# RCMX_Rev_00_BPS.net
KiCad netlist of a schematic drawn in EAGLE
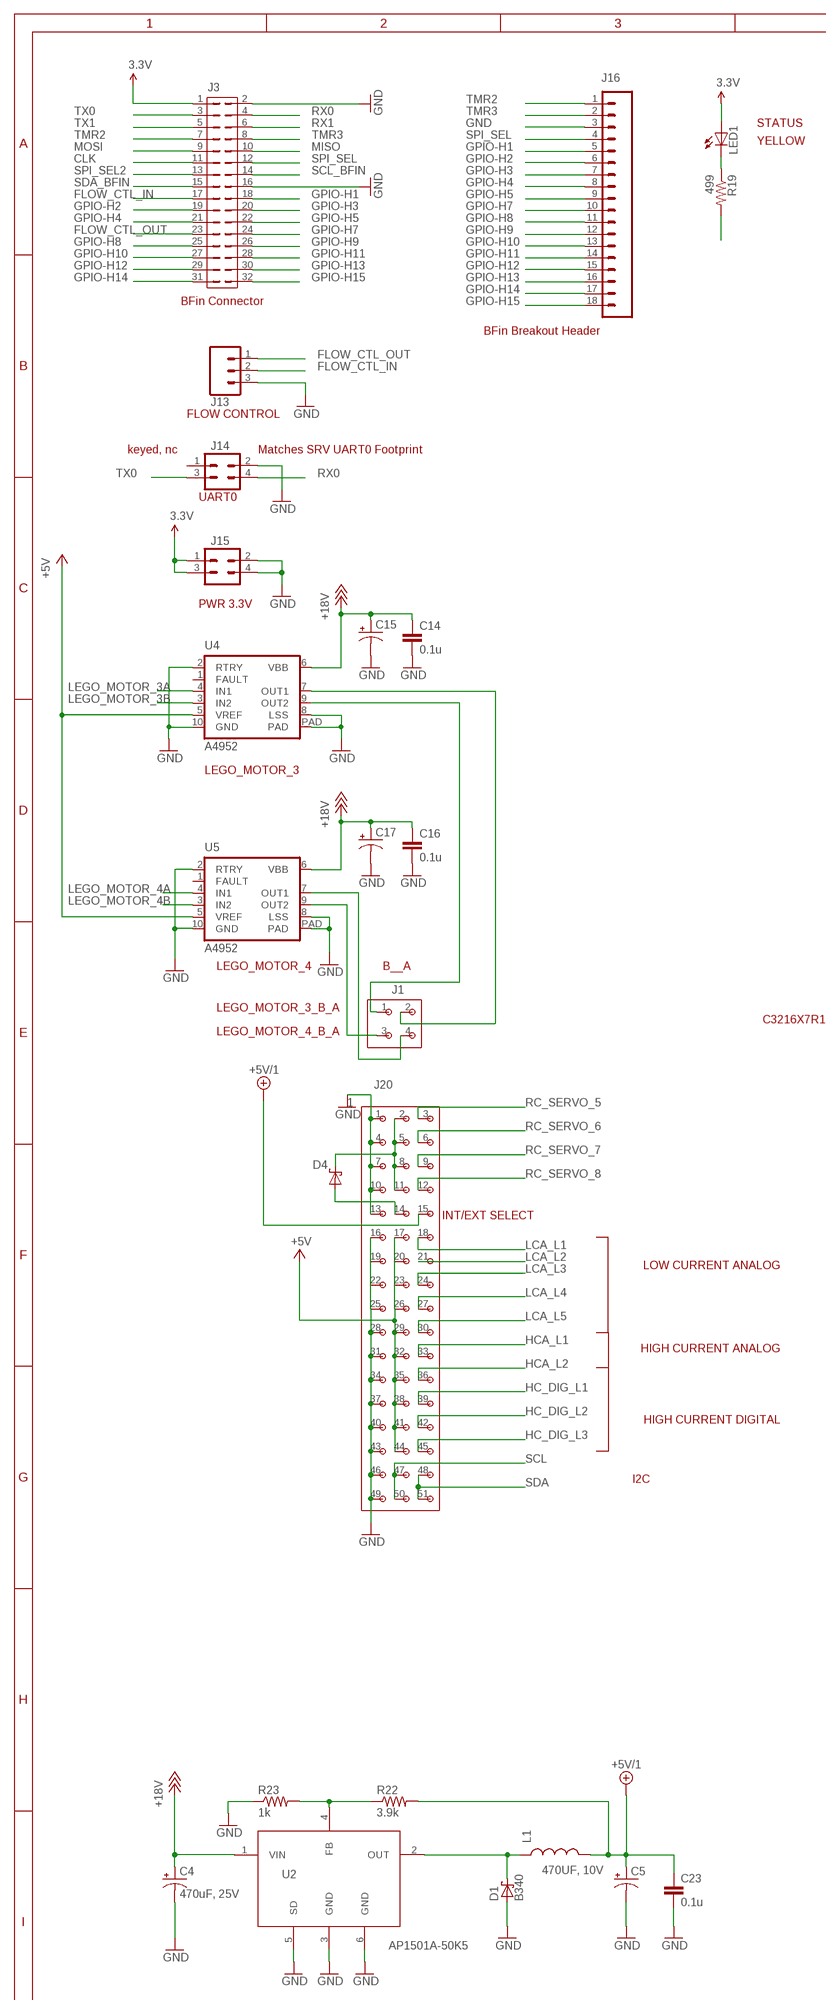
[diagram p0: schematic, sheet 1, part 1 of 2]
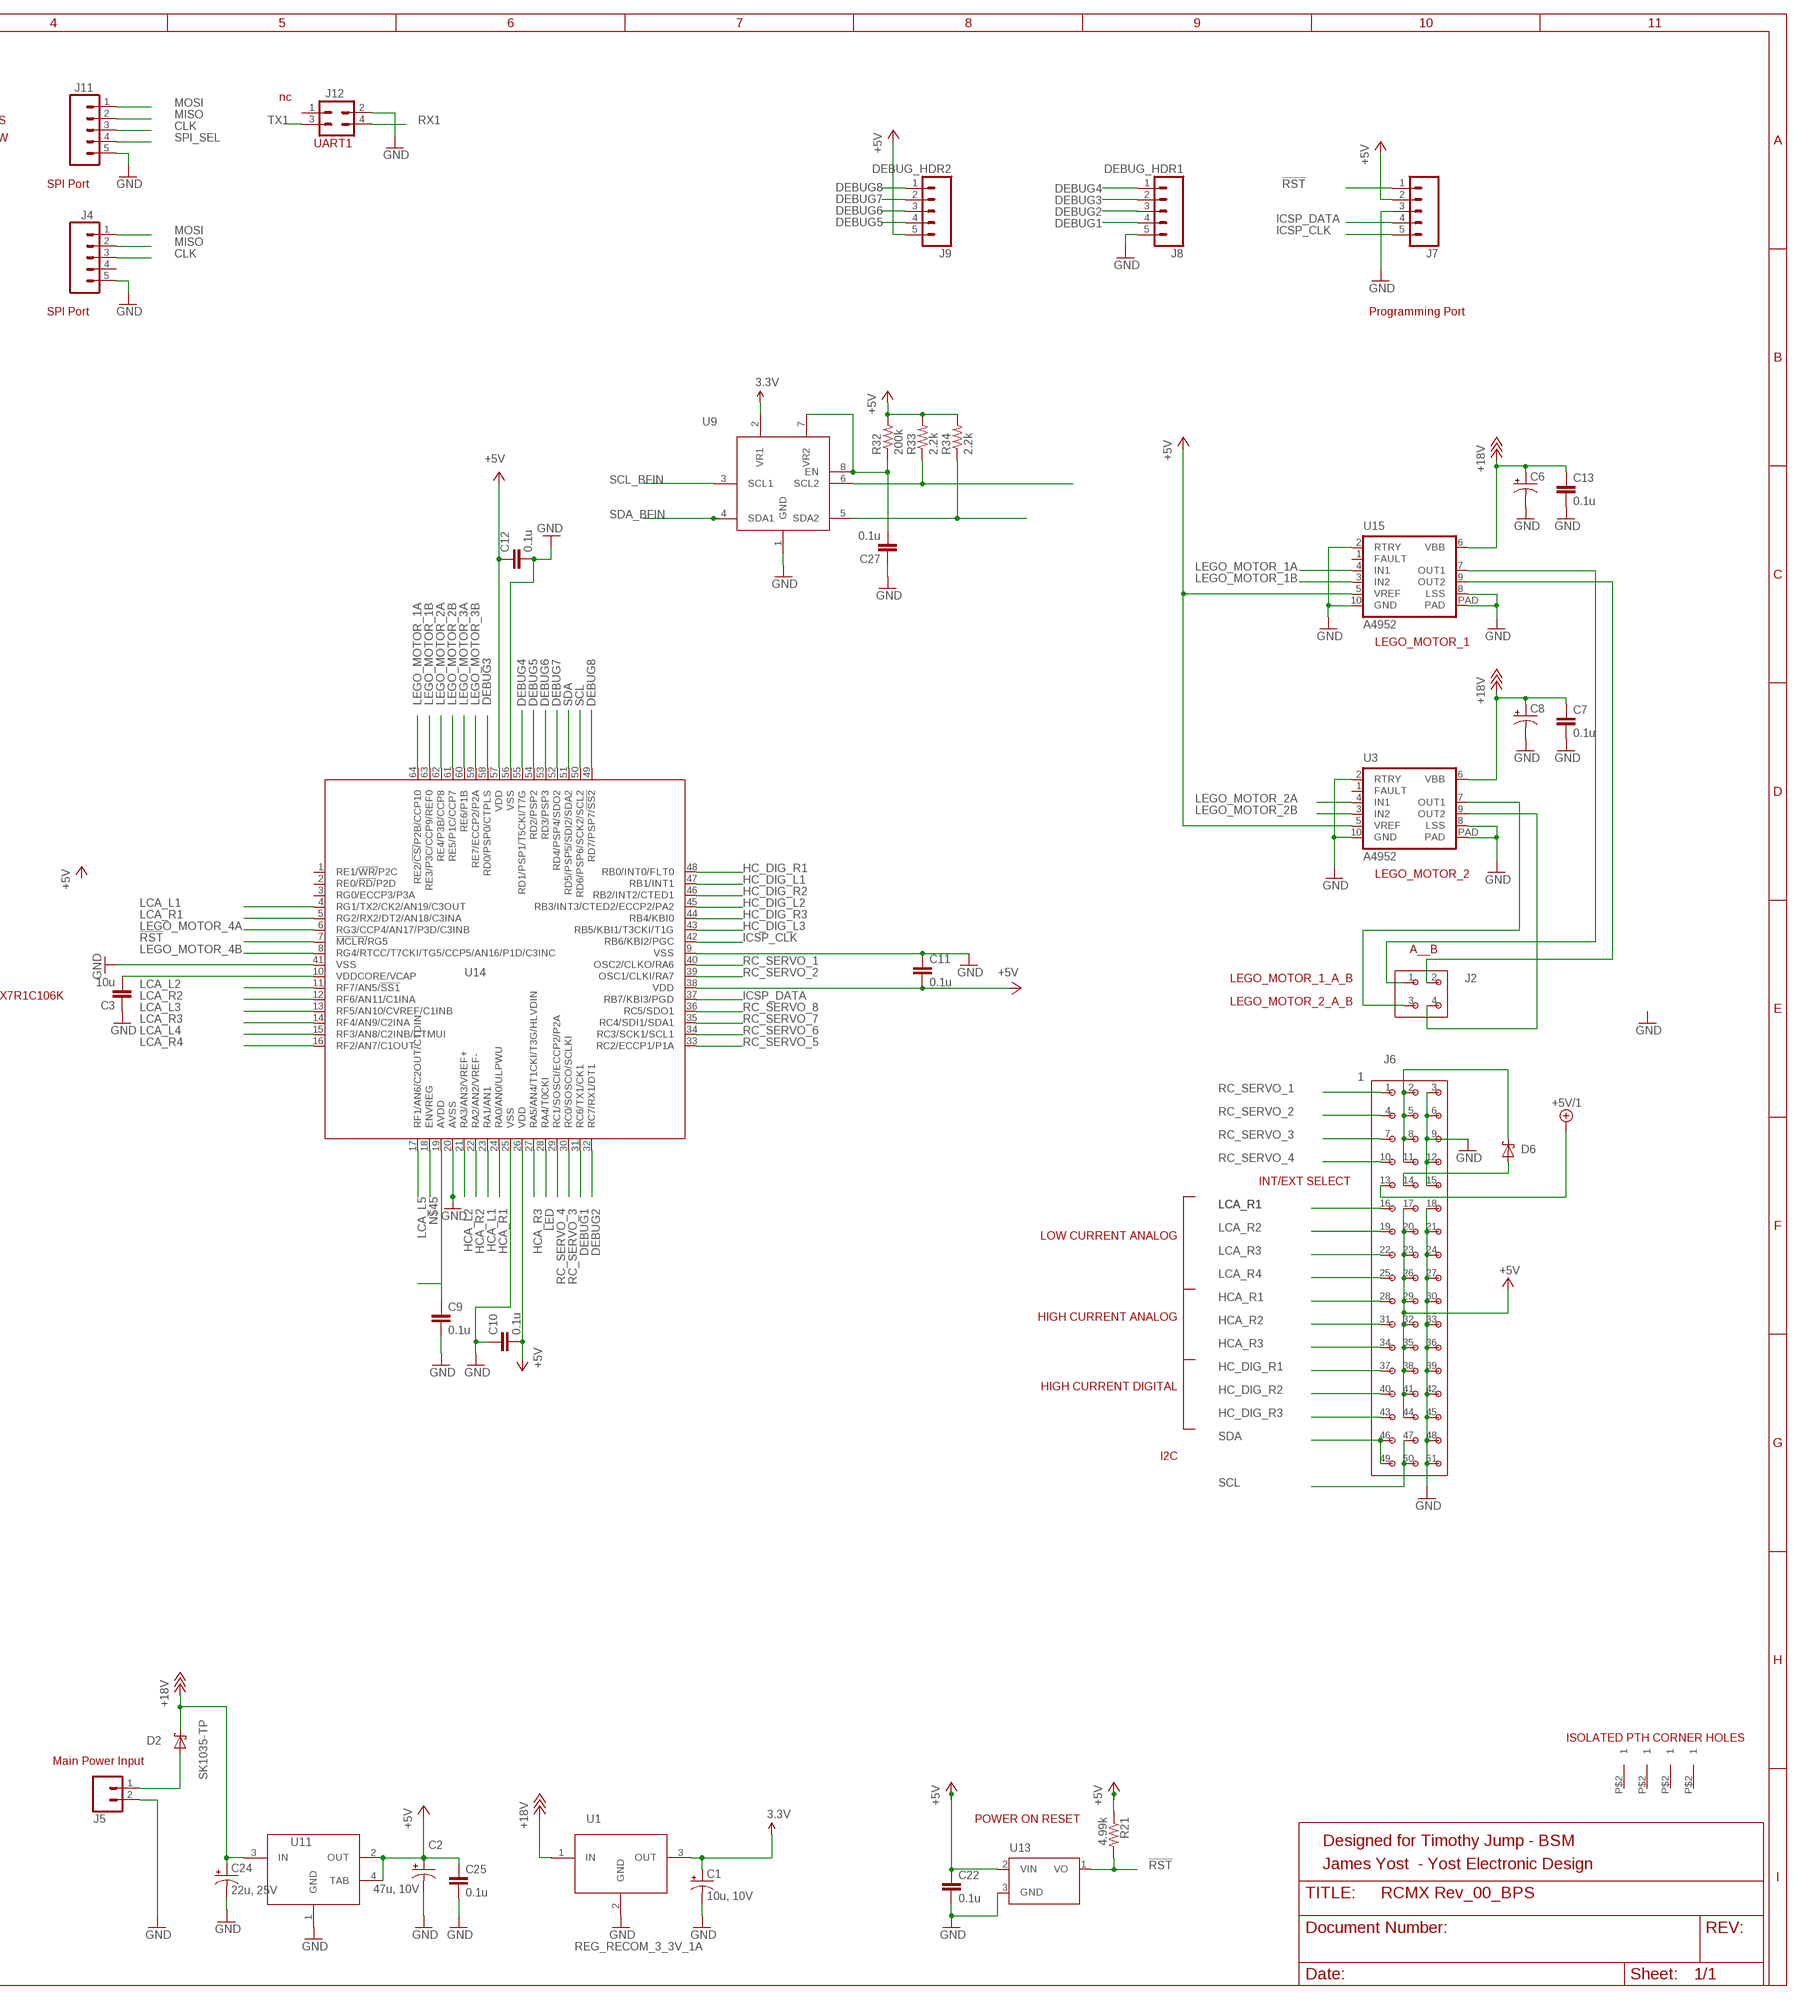
[diagram p1: schematic, sheet 1, part 2 of 2]

(export (version "E")
  (design (tool "Eeschema 10.0.6"))
  (components
    (comp (ref "C1")
      (value "10u, 10V")
      (footprint "eagle-import:EIA3216")
      (libsource (lib "eagle-import") (part "CAP_POL1206"))
    )
    (comp (ref "C2")
      (value "47u, 10V")
      (footprint "eagle-import:CAP1210_POL")
      (libsource (lib "eagle-import") (part "CAP_1210_POL"))
    )
    (comp (ref "C3")
      (value "10u")
      (footprint "eagle-import:1206")
      (libsource (lib "eagle-import") (part "CAP1206"))
    )
    (comp (ref "C4")
      (value "470uF, 25V")
      (footprint "eagle-import:PANASONIC_G")
      (libsource (lib "eagle-import") (part "CAP_POLG"))
    )
    (comp (ref "C5")
      (value "470UF, 10V")
      (footprint "eagle-import:PANASONIC_F")
      (libsource (lib "eagle-import") (part "CAP_ELT_PANASONIC_470UF"))
    )
    (comp (ref "C6")
      (value "CAP_POLD")
      (footprint "eagle-import:PANASONIC_D")
      (libsource (lib "eagle-import") (part "CAP_POLD"))
    )
    (comp (ref "C7")
      (value "0.1u")
      (footprint "eagle-import:0805")
      (libsource (lib "eagle-import") (part "CAP0805"))
    )
    (comp (ref "C8")
      (value "CAP_POLD")
      (footprint "eagle-import:PANASONIC_D")
      (libsource (lib "eagle-import") (part "CAP_POLD"))
    )
    (comp (ref "C9")
      (value "0.1u")
      (footprint "eagle-import:0805")
      (libsource (lib "eagle-import") (part "CAP0805"))
    )
    (comp (ref "C10")
      (value "0.1u")
      (footprint "eagle-import:0805")
      (libsource (lib "eagle-import") (part "CAP0805"))
    )
    (comp (ref "C11")
      (value "0.1u")
      (footprint "eagle-import:0805")
      (libsource (lib "eagle-import") (part "CAP0805"))
    )
    (comp (ref "C12")
      (value "0.1u")
      (footprint "eagle-import:0805")
      (libsource (lib "eagle-import") (part "CAP0805"))
    )
    (comp (ref "C13")
      (value "0.1u")
      (footprint "eagle-import:0805")
      (libsource (lib "eagle-import") (part "CAP0805"))
    )
    (comp (ref "C14")
      (value "0.1u")
      (footprint "eagle-import:0805")
      (libsource (lib "eagle-import") (part "CAP0805"))
    )
    (comp (ref "C15")
      (value "CAP_POLD")
      (footprint "eagle-import:PANASONIC_D")
      (libsource (lib "eagle-import") (part "CAP_POLD"))
    )
    (comp (ref "C16")
      (value "0.1u")
      (footprint "eagle-import:0805")
      (libsource (lib "eagle-import") (part "CAP0805"))
    )
    (comp (ref "C17")
      (value "CAP_POLD")
      (footprint "eagle-import:PANASONIC_D")
      (libsource (lib "eagle-import") (part "CAP_POLD"))
    )
    (comp (ref "C22")
      (value "0.1u")
      (footprint "eagle-import:0805")
      (libsource (lib "eagle-import") (part "CAP0805"))
    )
    (comp (ref "C23")
      (value "0.1u")
      (footprint "eagle-import:0805")
      (libsource (lib "eagle-import") (part "CAP0805"))
    )
    (comp (ref "C24")
      (value "22u, 25V")
      (footprint "eagle-import:CAP1210_POL")
      (libsource (lib "eagle-import") (part "CAP_1210_POL"))
    )
    (comp (ref "C25")
      (value "0.1u")
      (footprint "eagle-import:0805")
      (libsource (lib "eagle-import") (part "CAP0805"))
    )
    (comp (ref "C27")
      (value "0.1u")
      (footprint "eagle-import:0805")
      (libsource (lib "eagle-import") (part "CAP0805"))
    )
    (comp (ref "D1")
      (value "B340")
      (footprint "eagle-import:SMA_DO214AC")
      (libsource (lib "eagle-import") (part "B340"))
    )
    (comp (ref "D2")
      (value "SK1035-TP")
      (footprint "eagle-import:DO214AB")
      (libsource (lib "eagle-import") (part "SK1035-TP"))
    )
    (comp (ref "D4")
      (value "SK1035-TP")
      (footprint "eagle-import:DO214AB")
      (libsource (lib "eagle-import") (part "SK1035-TP"))
    )
    (comp (ref "D6")
      (value "SK1035-TP")
      (footprint "eagle-import:DO214AB")
      (libsource (lib "eagle-import") (part "SK1035-TP"))
    )
    (comp (ref "J1")
      (value "CON_2X2_0_100")
      (footprint "eagle-import:CON_2X2_0_100")
      (libsource (lib "eagle-import") (part "CON_2X2_0_100"))
    )
    (comp (ref "J2")
      (value "CON_2X2_0_100")
      (footprint "eagle-import:CON_2X2_0_100")
      (libsource (lib "eagle-import") (part "CON_2X2_0_100"))
    )
    (comp (ref "J3")
      (value "CON_2X16_0_100")
      (footprint "eagle-import:CON_2X16_0_100")
      (libsource (lib "eagle-import") (part "CON_2X16_0_100"))
    )
    (comp (ref "J4")
      (value "M05PTH")
      (footprint "eagle-import:1X05")
      (libsource (lib "eagle-import") (part "M05PTH"))
    )
    (comp (ref "J5")
      (value "M02NG")
      (footprint "eagle-import:1X02")
      (libsource (lib "eagle-import") (part "M02NG"))
    )
    (comp (ref "J6")
      (value "CON_3X17_0_100")
      (footprint "eagle-import:CON_3X17_0_100")
      (libsource (lib "eagle-import") (part "CON_3X17_0_100"))
    )
    (comp (ref "J7")
      (value "M05PTH")
      (footprint "eagle-import:1X05")
      (libsource (lib "eagle-import") (part "SparkFun-Connectors_M05PTH"))
    )
    (comp (ref "J8")
      (value "DEBUG_HDR1")
      (footprint "eagle-import:1X05")
      (libsource (lib "eagle-import") (part "SparkFun-Connectors_M05PTH"))
    )
    (comp (ref "J9")
      (value "DEBUG_HDR2")
      (footprint "eagle-import:1X05")
      (libsource (lib "eagle-import") (part "SparkFun-Connectors_M05PTH"))
    )
    (comp (ref "J11")
      (value "M05PTH")
      (footprint "eagle-import:1X05")
      (libsource (lib "eagle-import") (part "M05PTH"))
    )
    (comp (ref "J12")
      (value "CON2X2")
      (footprint "eagle-import:CON2X2")
      (libsource (lib "eagle-import") (part "CON2X2"))
    )
    (comp (ref "J13")
      (value "M03PTH")
      (footprint "eagle-import:1X03")
      (libsource (lib "eagle-import") (part "M03PTH"))
    )
    (comp (ref "J14")
      (value "CON2X2")
      (footprint "eagle-import:CON2X2")
      (libsource (lib "eagle-import") (part "CON2X2"))
    )
    (comp (ref "J15")
      (value "CON2X2")
      (footprint "eagle-import:CON2X2")
      (libsource (lib "eagle-import") (part "CON2X2"))
    )
    (comp (ref "J16")
      (value "CON1X18")
      (footprint "eagle-import:CON1X18")
      (libsource (lib "eagle-import") (part "CON1X18"))
    )
    (comp (ref "J20")
      (value "CON_3X17_0_100")
      (footprint "eagle-import:CON_3X17_0_100")
      (libsource (lib "eagle-import") (part "CON_3X17_0_100"))
    )
    (comp (ref "L1")
      (value "IND_47UH_COILTRONICS_2_95A")
      (footprint "eagle-import:IND_PADS_SMT")
      (libsource (lib "eagle-import") (part "IND_47UH_COILTRONICS_2_95A"))
    )
    (comp (ref "LED1")
      (value "LEDCHIP-LED0805")
      (footprint "eagle-import:CHIP-LED0805")
      (libsource (lib "eagle-import") (part "LEDCHIP-LED0805"))
    )
    (comp (ref "R19")
      (value "499")
      (footprint "eagle-import:0805")
      (libsource (lib "eagle-import") (part "RESISTOR"))
    )
    (comp (ref "R21")
      (value "4.99k")
      (footprint "eagle-import:0805")
      (libsource (lib "eagle-import") (part "RESISTOR"))
    )
    (comp (ref "R22")
      (value "3.9k")
      (footprint "eagle-import:0805")
      (libsource (lib "eagle-import") (part "RESISTOR"))
    )
    (comp (ref "R23")
      (value "1k")
      (footprint "eagle-import:0805")
      (libsource (lib "eagle-import") (part "RESISTOR"))
    )
    (comp (ref "R32")
      (value "200k")
      (footprint "eagle-import:0805")
      (libsource (lib "eagle-import") (part "RESISTOR"))
    )
    (comp (ref "R33")
      (value "2.2k")
      (footprint "eagle-import:0805")
      (libsource (lib "eagle-import") (part "RESISTOR"))
    )
    (comp (ref "R34")
      (value "2.2k")
      (footprint "eagle-import:0805")
      (libsource (lib "eagle-import") (part "RESISTOR"))
    )
    (comp (ref "U$1")
      (value "GNDPAD")
      (footprint "eagle-import:GNDPAD")
      (libsource (lib "eagle-import") (part "GNDPAD"))
    )
    (comp (ref "U$2")
      (value "GNDPAD")
      (footprint "eagle-import:GNDPAD")
      (libsource (lib "eagle-import") (part "GNDPAD"))
    )
    (comp (ref "U$7")
      (value "GNDPAD")
      (footprint "eagle-import:GNDPAD")
      (libsource (lib "eagle-import") (part "GNDPAD"))
    )
    (comp (ref "U$8")
      (value "GNDPAD")
      (footprint "eagle-import:GNDPAD")
      (libsource (lib "eagle-import") (part "GNDPAD"))
    )
    (comp (ref "U1")
      (value "REG_RECOM_3_3V_1A")
      (footprint "eagle-import:REG_RECOM_3_3V_1A")
      (libsource (lib "eagle-import") (part "REG_RECOM_3_3V_1A"))
    )
    (comp (ref "U2")
      (value "AP1501A-50K5")
      (footprint "eagle-import:TO263-5")
      (libsource (lib "eagle-import") (part "AP1501A-50K5"))
    )
    (comp (ref "U3")
      (value "A4952")
      (footprint "eagle-import:MSOP10_W_THERMAL_PAD")
      (libsource (lib "eagle-import") (part "A4952"))
    )
    (comp (ref "U4")
      (value "A4952")
      (footprint "eagle-import:MSOP10_W_THERMAL_PAD")
      (libsource (lib "eagle-import") (part "A4952"))
    )
    (comp (ref "U5")
      (value "A4952")
      (footprint "eagle-import:MSOP10_W_THERMAL_PAD")
      (libsource (lib "eagle-import") (part "A4952"))
    )
    (comp (ref "U9")
      (value "PCA9306DCT")
      (footprint "eagle-import:TEST08")
      (libsource (lib "eagle-import") (part "PCA9306DCT"))
    )
    (comp (ref "U11")
      (value "TLV1117-5")
      (footprint "eagle-import:SOT223")
      (libsource (lib "eagle-import") (part "TLV1117-5"))
    )
    (comp (ref "U13")
      (value "MCP130T")
      (footprint "eagle-import:SOT23")
      (libsource (lib "eagle-import") (part "MCP130T"))
    )
    (comp (ref "U14")
      (value "MICRO_C_PIC18F65K22")
      (footprint "eagle-import:64PIN_TQFP_10X10X1MM")
      (libsource (lib "eagle-import") (part "MICRO_C_PIC18F65K22"))
    )
    (comp (ref "U15")
      (value "A4952")
      (footprint "eagle-import:MSOP10_W_THERMAL_PAD")
      (libsource (lib "eagle-import") (part "A4952"))
    )
  )
  (nets
    (net (code "1") (name "+5V") (class "Default")
      (node (ref "C10") (pin "2") (pinfunction "2_2") (pintype "passive"))
      (node (ref "C11") (pin "2") (pinfunction "2_2") (pintype "passive"))
      (node (ref "C12") (pin "1") (pinfunction "1_1") (pintype "passive"))
      (node (ref "C2") (pin "1") (pinfunction "+_1") (pintype "passive"))
      (node (ref "C22") (pin "1") (pinfunction "1_1") (pintype "passive"))
      (node (ref "C25") (pin "1") (pinfunction "1_1") (pintype "passive"))
      (node (ref "J20") (pin "17") (pinfunction "17_17") (pintype "passive"))
      (node (ref "J20") (pin "20") (pinfunction "20_20") (pintype "passive"))
      (node (ref "J20") (pin "23") (pinfunction "23_23") (pintype "passive"))
      (node (ref "J20") (pin "26") (pinfunction "26_26") (pintype "passive"))
      (node (ref "J20") (pin "29") (pinfunction "29_29") (pintype "passive"))
      (node (ref "J20") (pin "32") (pinfunction "32_32") (pintype "passive"))
      (node (ref "J20") (pin "35") (pinfunction "35_35") (pintype "passive"))
      (node (ref "J20") (pin "38") (pinfunction "38_38") (pintype "passive"))
      (node (ref "J20") (pin "41") (pinfunction "41_41") (pintype "passive"))
      (node (ref "J20") (pin "44") (pinfunction "44_44") (pintype "passive"))
      (node (ref "J6") (pin "17") (pinfunction "17_17") (pintype "passive"))
      (node (ref "J6") (pin "20") (pinfunction "20_20") (pintype "passive"))
      (node (ref "J6") (pin "23") (pinfunction "23_23") (pintype "passive"))
      (node (ref "J6") (pin "26") (pinfunction "26_26") (pintype "passive"))
      (node (ref "J6") (pin "29") (pinfunction "29_29") (pintype "passive"))
      (node (ref "J6") (pin "32") (pinfunction "32_32") (pintype "passive"))
      (node (ref "J6") (pin "35") (pinfunction "35_35") (pintype "passive"))
      (node (ref "J6") (pin "38") (pinfunction "38_38") (pintype "passive"))
      (node (ref "J6") (pin "41") (pinfunction "41_41") (pintype "passive"))
      (node (ref "J6") (pin "44") (pinfunction "44_44") (pintype "passive"))
      (node (ref "J7") (pin "2") (pinfunction "2_2") (pintype "passive"))
      (node (ref "J9") (pin "5") (pinfunction "5_5") (pintype "passive"))
      (node (ref "R21") (pin "1") (pinfunction "1_1") (pintype "passive"))
      (node (ref "R32") (pin "2") (pinfunction "2_2") (pintype "passive"))
      (node (ref "R33") (pin "2") (pinfunction "2_2") (pintype "passive"))
      (node (ref "R34") (pin "2") (pinfunction "2_2") (pintype "passive"))
      (node (ref "U11") (pin "2") (pinfunction "OUT_2") (pintype "bidirectional"))
      (node (ref "U11") (pin "4") (pinfunction "TAB_4") (pintype "bidirectional"))
      (node (ref "U13") (pin "2") (pinfunction "VIN_2") (pintype "input"))
      (node (ref "U14") (pin "26") (pinfunction "VDD_26") (pintype "power_in"))
      (node (ref "U14") (pin "38") (pinfunction "VDD_38") (pintype "power_in"))
      (node (ref "U14") (pin "57") (pinfunction "VDD_57") (pintype "power_in"))
      (node (ref "U15") (pin "5") (pinfunction "VREF_5") (pintype "passive"))
      (node (ref "U3") (pin "5") (pinfunction "VREF_5") (pintype "passive"))
      (node (ref "U4") (pin "5") (pinfunction "VREF_5") (pintype "passive"))
      (node (ref "U5") (pin "5") (pinfunction "VREF_5") (pintype "passive"))
    )
    (net (code "2") (name "+5V{slash}1") (class "Default")
      (node (ref "C23") (pin "1") (pinfunction "1_1") (pintype "passive"))
      (node (ref "C5") (pin "+") (pinfunction "+_+") (pintype "passive"))
      (node (ref "J20") (pin "15") (pinfunction "15_15") (pintype "passive"))
      (node (ref "J6") (pin "13") (pinfunction "13_13") (pintype "passive"))
      (node (ref "L1") (pin "2") (pinfunction "2_2") (pintype "passive"))
      (node (ref "R22") (pin "2") (pinfunction "2_2") (pintype "passive"))
    )
    (net (code "3") (name "+18V") (class "Default")
      (node (ref "C13") (pin "1") (pinfunction "1_1") (pintype "passive"))
      (node (ref "C14") (pin "1") (pinfunction "1_1") (pintype "passive"))
      (node (ref "C15") (pin "+") (pinfunction "+_+") (pintype "passive"))
      (node (ref "C16") (pin "1") (pinfunction "1_1") (pintype "passive"))
      (node (ref "C17") (pin "+") (pinfunction "+_+") (pintype "passive"))
      (node (ref "C24") (pin "1") (pinfunction "+_1") (pintype "passive"))
      (node (ref "C4") (pin "+") (pinfunction "+_+") (pintype "passive"))
      (node (ref "C6") (pin "+") (pinfunction "+_+") (pintype "passive"))
      (node (ref "C7") (pin "1") (pinfunction "1_1") (pintype "passive"))
      (node (ref "C8") (pin "+") (pinfunction "+_+") (pintype "passive"))
      (node (ref "D2") (pin "1") (pinfunction "C_1") (pintype "passive"))
      (node (ref "U1") (pin "1") (pinfunction "IN_1") (pintype "bidirectional"))
      (node (ref "U11") (pin "3") (pinfunction "IN_3") (pintype "bidirectional"))
      (node (ref "U15") (pin "6") (pinfunction "VBB_6") (pintype "input"))
      (node (ref "U2") (pin "1") (pinfunction "VIN_1") (pintype "bidirectional"))
      (node (ref "U3") (pin "6") (pinfunction "VBB_6") (pintype "input"))
      (node (ref "U4") (pin "6") (pinfunction "VBB_6") (pintype "input"))
      (node (ref "U5") (pin "6") (pinfunction "VBB_6") (pintype "input"))
    )
    (net (code "4") (name "/CLK") (class "Default")
      (node (ref "J11") (pin "3") (pinfunction "3_3") (pintype "passive"))
      (node (ref "J3") (pin "11") (pinfunction "11_11") (pintype "passive"))
      (node (ref "J4") (pin "3") (pinfunction "3_3") (pintype "passive"))
    )
    (net (code "5") (name "/DEBUG1") (class "Default")
      (node (ref "J8") (pin "4") (pinfunction "4_4") (pintype "passive"))
      (node (ref "U14") (pin "31") (pinfunction "RC6/TX1/CK1_31") (pintype "bidirectional"))
    )
    (net (code "6") (name "/DEBUG2") (class "Default")
      (node (ref "J8") (pin "3") (pinfunction "3_3") (pintype "passive"))
      (node (ref "U14") (pin "32") (pinfunction "RC7/RX1/DT1_32") (pintype "bidirectional"))
    )
    (net (code "7") (name "/DEBUG3") (class "Default")
      (node (ref "J8") (pin "2") (pinfunction "2_2") (pintype "passive"))
      (node (ref "U14") (pin "58") (pinfunction "RD0/PSP0/CTPLS_58") (pintype "bidirectional"))
    )
    (net (code "8") (name "/DEBUG4") (class "Default")
      (node (ref "J8") (pin "1") (pinfunction "1_1") (pintype "passive"))
      (node (ref "U14") (pin "55") (pinfunction "RD1/PSP1/T5CKI/T7G_55") (pintype "bidirectional"))
    )
    (net (code "9") (name "/DEBUG5") (class "Default")
      (node (ref "J9") (pin "4") (pinfunction "4_4") (pintype "passive"))
      (node (ref "U14") (pin "54") (pinfunction "RD2/PSP2_54") (pintype "bidirectional"))
    )
    (net (code "10") (name "/DEBUG6") (class "Default")
      (node (ref "J9") (pin "3") (pinfunction "3_3") (pintype "passive"))
      (node (ref "U14") (pin "53") (pinfunction "RD3/PSP3_53") (pintype "bidirectional"))
    )
    (net (code "11") (name "/DEBUG7") (class "Default")
      (node (ref "J9") (pin "2") (pinfunction "2_2") (pintype "passive"))
      (node (ref "U14") (pin "52") (pinfunction "RD4/PSP4/SDO2_52") (pintype "bidirectional"))
    )
    (net (code "12") (name "/DEBUG8") (class "Default")
      (node (ref "J9") (pin "1") (pinfunction "1_1") (pintype "passive"))
      (node (ref "U14") (pin "49") (pinfunction "RD7/PSP7/~{SS2}_49") (pintype "bidirectional"))
    )
    (net (code "13") (name "/FLOW_CTL_IN") (class "Default")
      (node (ref "J13") (pin "2") (pinfunction "2_2") (pintype "passive"))
      (node (ref "J3") (pin "17") (pinfunction "17_17") (pintype "passive"))
    )
    (net (code "14") (name "/FLOW_CTL_OUT") (class "Default")
      (node (ref "J13") (pin "1") (pinfunction "1_1") (pintype "passive"))
      (node (ref "J3") (pin "23") (pinfunction "23_23") (pintype "passive"))
    )
    (net (code "15") (name "/GPIO-H1") (class "Default")
      (node (ref "J16") (pin "5") (pinfunction "5_5") (pintype "passive"))
      (node (ref "J3") (pin "18") (pinfunction "18_18") (pintype "passive"))
    )
    (net (code "16") (name "/GPIO-H2") (class "Default")
      (node (ref "J16") (pin "6") (pinfunction "6_6") (pintype "passive"))
      (node (ref "J3") (pin "19") (pinfunction "19_19") (pintype "passive"))
    )
    (net (code "17") (name "/GPIO-H3") (class "Default")
      (node (ref "J16") (pin "7") (pinfunction "7_7") (pintype "passive"))
      (node (ref "J3") (pin "20") (pinfunction "20_20") (pintype "passive"))
    )
    (net (code "18") (name "/GPIO-H4") (class "Default")
      (node (ref "J16") (pin "8") (pinfunction "8_8") (pintype "passive"))
      (node (ref "J3") (pin "21") (pinfunction "21_21") (pintype "passive"))
    )
    (net (code "19") (name "/GPIO-H5") (class "Default")
      (node (ref "J16") (pin "9") (pinfunction "9_9") (pintype "passive"))
      (node (ref "J3") (pin "22") (pinfunction "22_22") (pintype "passive"))
    )
    (net (code "20") (name "/GPIO-H7") (class "Default")
      (node (ref "J16") (pin "10") (pinfunction "10_10") (pintype "passive"))
      (node (ref "J3") (pin "24") (pinfunction "24_24") (pintype "passive"))
    )
    (net (code "21") (name "/GPIO-H8") (class "Default")
      (node (ref "J16") (pin "11") (pinfunction "11_11") (pintype "passive"))
      (node (ref "J3") (pin "25") (pinfunction "25_25") (pintype "passive"))
    )
    (net (code "22") (name "/GPIO-H9") (class "Default")
      (node (ref "J16") (pin "12") (pinfunction "12_12") (pintype "passive"))
      (node (ref "J3") (pin "26") (pinfunction "26_26") (pintype "passive"))
    )
    (net (code "23") (name "/GPIO-H10") (class "Default")
      (node (ref "J16") (pin "13") (pinfunction "13_13") (pintype "passive"))
      (node (ref "J3") (pin "27") (pinfunction "27_27") (pintype "passive"))
    )
    (net (code "24") (name "/GPIO-H11") (class "Default")
      (node (ref "J16") (pin "14") (pinfunction "14_14") (pintype "passive"))
      (node (ref "J3") (pin "28") (pinfunction "28_28") (pintype "passive"))
    )
    (net (code "25") (name "/GPIO-H12") (class "Default")
      (node (ref "J16") (pin "15") (pinfunction "15_15") (pintype "passive"))
      (node (ref "J3") (pin "29") (pinfunction "29_29") (pintype "passive"))
    )
    (net (code "26") (name "/GPIO-H13") (class "Default")
      (node (ref "J16") (pin "16") (pinfunction "16_16") (pintype "passive"))
      (node (ref "J3") (pin "30") (pinfunction "30_30") (pintype "passive"))
    )
    (net (code "27") (name "/GPIO-H14") (class "Default")
      (node (ref "J16") (pin "17") (pinfunction "17_17") (pintype "passive"))
      (node (ref "J3") (pin "31") (pinfunction "31_31") (pintype "passive"))
    )
    (net (code "28") (name "/GPIO-H15") (class "Default")
      (node (ref "J16") (pin "18") (pinfunction "18_18") (pintype "passive"))
      (node (ref "J3") (pin "32") (pinfunction "32_32") (pintype "passive"))
    )
    (net (code "29") (name "/HCA_L1") (class "Default")
      (node (ref "J20") (pin "33") (pinfunction "33_33") (pintype "passive"))
      (node (ref "U14") (pin "23") (pinfunction "RA1/AN1_23") (pintype "bidirectional"))
    )
    (net (code "30") (name "/HCA_L2") (class "Default")
      (node (ref "J20") (pin "36") (pinfunction "36_36") (pintype "passive"))
      (node (ref "U14") (pin "21") (pinfunction "RA3/AN3/VREF+_21") (pintype "bidirectional"))
    )
    (net (code "31") (name "/HCA_R1") (class "Default")
      (node (ref "J6") (pin "28") (pinfunction "28_28") (pintype "passive"))
      (node (ref "U14") (pin "24") (pinfunction "RA0/AN0/ULPWU_24") (pintype "bidirectional"))
    )
    (net (code "32") (name "/HCA_R2") (class "Default")
      (node (ref "J6") (pin "31") (pinfunction "31_31") (pintype "passive"))
      (node (ref "U14") (pin "22") (pinfunction "RA2/AN2/VREF-_22") (pintype "bidirectional"))
    )
    (net (code "33") (name "/HCA_R3") (class "Default")
      (node (ref "J6") (pin "34") (pinfunction "34_34") (pintype "passive"))
      (node (ref "U14") (pin "27") (pinfunction "RA5/AN4/T1CKI/T3G/HLVDIN_27") (pintype "bidirectional"))
    )
    (net (code "34") (name "/HC_DIG_L1") (class "Default")
      (node (ref "J20") (pin "39") (pinfunction "39_39") (pintype "passive"))
      (node (ref "U14") (pin "47") (pinfunction "RB1/INT1_47") (pintype "bidirectional"))
    )
    (net (code "35") (name "/HC_DIG_L2") (class "Default")
      (node (ref "J20") (pin "42") (pinfunction "42_42") (pintype "passive"))
      (node (ref "U14") (pin "45") (pinfunction "RB3/INT3/CTED2/ECCP2/PA2_45") (pintype "bidirectional"))
    )
    (net (code "36") (name "/HC_DIG_L3") (class "Default")
      (node (ref "J20") (pin "45") (pinfunction "45_45") (pintype "passive"))
      (node (ref "U14") (pin "43") (pinfunction "RB5/KBI1/T3CKI/T1G_43") (pintype "bidirectional"))
    )
    (net (code "37") (name "/HC_DIG_R1") (class "Default")
      (node (ref "J6") (pin "37") (pinfunction "37_37") (pintype "passive"))
      (node (ref "U14") (pin "48") (pinfunction "RB0/INT0/FLT0_48") (pintype "bidirectional"))
    )
    (net (code "38") (name "/HC_DIG_R2") (class "Default")
      (node (ref "J6") (pin "40") (pinfunction "40_40") (pintype "passive"))
      (node (ref "U14") (pin "46") (pinfunction "RB2/INT2/CTED1_46") (pintype "bidirectional"))
    )
    (net (code "39") (name "/HC_DIG_R3") (class "Default")
      (node (ref "J6") (pin "43") (pinfunction "43_43") (pintype "passive"))
      (node (ref "U14") (pin "44") (pinfunction "RB4/KBI0_44") (pintype "bidirectional"))
    )
    (net (code "40") (name "/ICSP_CLK") (class "Default")
      (node (ref "J7") (pin "5") (pinfunction "5_5") (pintype "passive"))
      (node (ref "U14") (pin "42") (pinfunction "RB6/KBI2/PGC_42") (pintype "bidirectional"))
    )
    (net (code "41") (name "/ICSP_DATA") (class "Default")
      (node (ref "J7") (pin "4") (pinfunction "4_4") (pintype "passive"))
      (node (ref "U14") (pin "37") (pinfunction "RB7/KBI3/PGD_37") (pintype "bidirectional"))
    )
    (net (code "42") (name "/LCA_L1") (class "Default")
      (node (ref "J20") (pin "18") (pinfunction "18_18") (pintype "passive"))
      (node (ref "U14") (pin "4") (pinfunction "RG1/TX2/CK2/AN19/C3OUT_4") (pintype "bidirectional"))
    )
    (net (code "43") (name "/LCA_L2") (class "Default")
      (node (ref "J20") (pin "21") (pinfunction "21_21") (pintype "passive"))
      (node (ref "U14") (pin "11") (pinfunction "RF7/AN5/~{SS1}_11") (pintype "bidirectional"))
    )
    (net (code "44") (name "/LCA_L3") (class "Default")
      (node (ref "J20") (pin "24") (pinfunction "24_24") (pintype "passive"))
      (node (ref "U14") (pin "13") (pinfunction "RF5/AN10/CVREF/C1INB_13") (pintype "bidirectional"))
    )
    (net (code "45") (name "/LCA_L4") (class "Default")
      (node (ref "J20") (pin "27") (pinfunction "27_27") (pintype "passive"))
      (node (ref "U14") (pin "15") (pinfunction "RF3/AN8/C2INB/CTMUI_15") (pintype "bidirectional"))
    )
    (net (code "46") (name "/LCA_L5") (class "Default")
      (node (ref "J20") (pin "30") (pinfunction "30_30") (pintype "passive"))
      (node (ref "U14") (pin "17") (pinfunction "RF1/AN6/C2OUT/CTDIN_17") (pintype "bidirectional"))
    )
    (net (code "47") (name "/LCA_R1") (class "Default")
      (node (ref "J6") (pin "16") (pinfunction "16_16") (pintype "passive"))
      (node (ref "U14") (pin "5") (pinfunction "RG2/RX2/DT2/AN18/C3INA_5") (pintype "bidirectional"))
    )
    (net (code "48") (name "/LCA_R2") (class "Default")
      (node (ref "J6") (pin "19") (pinfunction "19_19") (pintype "passive"))
      (node (ref "U14") (pin "12") (pinfunction "RF6/AN11/C1INA_12") (pintype "bidirectional"))
    )
    (net (code "49") (name "/LCA_R3") (class "Default")
      (node (ref "J6") (pin "22") (pinfunction "22_22") (pintype "passive"))
      (node (ref "U14") (pin "14") (pinfunction "RF4/AN9/C2INA_14") (pintype "bidirectional"))
    )
    (net (code "50") (name "/LCA_R4") (class "Default")
      (node (ref "J6") (pin "25") (pinfunction "25_25") (pintype "passive"))
      (node (ref "U14") (pin "16") (pinfunction "RF2/AN7/C1OUT_16") (pintype "bidirectional"))
    )
    (net (code "51") (name "/LED") (class "Default")
      (node (ref "U14") (pin "28") (pinfunction "RA4/T0CKI_28") (pintype "bidirectional"))
    )
    (net (code "52") (name "/LEGO_MOTOR_1A") (class "Default")
      (node (ref "U14") (pin "64") (pinfunction "RE2/~{CS/}P2B/CCP10_64") (pintype "bidirectional"))
      (node (ref "U15") (pin "4") (pinfunction "IN1_4") (pintype "input"))
    )
    (net (code "53") (name "/LEGO_MOTOR_1B") (class "Default")
      (node (ref "U14") (pin "63") (pinfunction "RE3/P3C/CCP9/REF0_63") (pintype "bidirectional"))
      (node (ref "U15") (pin "3") (pinfunction "IN2_3") (pintype "input"))
    )
    (net (code "54") (name "/LEGO_MOTOR_2A") (class "Default")
      (node (ref "U14") (pin "62") (pinfunction "RE4/P3B/CCP8_62") (pintype "bidirectional"))
      (node (ref "U3") (pin "4") (pinfunction "IN1_4") (pintype "input"))
    )
    (net (code "55") (name "/LEGO_MOTOR_2B") (class "Default")
      (node (ref "U14") (pin "61") (pinfunction "RE5/P1C/CCP7_61") (pintype "bidirectional"))
      (node (ref "U3") (pin "3") (pinfunction "IN2_3") (pintype "input"))
    )
    (net (code "56") (name "/LEGO_MOTOR_3A") (class "Default")
      (node (ref "U14") (pin "60") (pinfunction "RE6/P1B_60") (pintype "bidirectional"))
      (node (ref "U4") (pin "4") (pinfunction "IN1_4") (pintype "input"))
    )
    (net (code "57") (name "/LEGO_MOTOR_3B") (class "Default")
      (node (ref "U14") (pin "59") (pinfunction "RE7/ECCP2/P2A_59") (pintype "bidirectional"))
      (node (ref "U4") (pin "3") (pinfunction "IN2_3") (pintype "input"))
    )
    (net (code "58") (name "/LEGO_MOTOR_4A") (class "Default")
      (node (ref "U14") (pin "6") (pinfunction "RG3/CCP4/AN17/P3D/C3INB_6") (pintype "bidirectional"))
      (node (ref "U5") (pin "4") (pinfunction "IN1_4") (pintype "input"))
    )
    (net (code "59") (name "/LEGO_MOTOR_4B") (class "Default")
      (node (ref "U14") (pin "8") (pinfunction "RG4/RTCC/T7CKI/TG5/CCP5/AN16/P1D/C3INC_8") (pintype "bidirectional"))
      (node (ref "U5") (pin "3") (pinfunction "IN2_3") (pintype "input"))
    )
    (net (code "60") (name "/MISO") (class "Default")
      (node (ref "J11") (pin "2") (pinfunction "2_2") (pintype "passive"))
      (node (ref "J3") (pin "10") (pinfunction "10_10") (pintype "passive"))
      (node (ref "J4") (pin "2") (pinfunction "2_2") (pintype "passive"))
    )
    (net (code "61") (name "/MOSI") (class "Default")
      (node (ref "J11") (pin "1") (pinfunction "1_1") (pintype "passive"))
      (node (ref "J3") (pin "9") (pinfunction "9_9") (pintype "passive"))
      (node (ref "J4") (pin "1") (pinfunction "1_1") (pintype "passive"))
    )
    (net (code "62") (name "/N$45") (class "Default")
      (node (ref "U14") (pin "18") (pinfunction "ENVREG_18") (pintype "input"))
    )
    (net (code "63") (name "/RC_SERVO_1") (class "Default")
      (node (ref "J6") (pin "1") (pinfunction "1_1") (pintype "passive"))
      (node (ref "U14") (pin "40") (pinfunction "OSC2/CLKO/RA6_40") (pintype "output"))
    )
    (net (code "64") (name "/RC_SERVO_2") (class "Default")
      (node (ref "J6") (pin "4") (pinfunction "4_4") (pintype "passive"))
      (node (ref "U14") (pin "39") (pinfunction "OSC1/CLKI/RA7_39") (pintype "input"))
    )
    (net (code "65") (name "/RC_SERVO_3") (class "Default")
      (node (ref "J6") (pin "7") (pinfunction "7_7") (pintype "passive"))
      (node (ref "U14") (pin "30") (pinfunction "RC0/SOSCO/SCLKI_30") (pintype "bidirectional"))
    )
    (net (code "66") (name "/RC_SERVO_4") (class "Default")
      (node (ref "J6") (pin "10") (pinfunction "10_10") (pintype "passive"))
      (node (ref "U14") (pin "29") (pinfunction "RC1/SOSCI/ECCP2/P2A_29") (pintype "bidirectional"))
    )
    (net (code "67") (name "/RC_SERVO_5") (class "Default")
      (node (ref "J20") (pin "3") (pinfunction "3_3") (pintype "passive"))
      (node (ref "U14") (pin "33") (pinfunction "RC2/ECCP1/P1A_33") (pintype "bidirectional"))
    )
    (net (code "68") (name "/RC_SERVO_6") (class "Default")
      (node (ref "J20") (pin "6") (pinfunction "6_6") (pintype "passive"))
      (node (ref "U14") (pin "34") (pinfunction "RC3/SCK1/SCL1_34") (pintype "bidirectional"))
    )
    (net (code "69") (name "/RC_SERVO_7") (class "Default")
      (node (ref "J20") (pin "9") (pinfunction "9_9") (pintype "passive"))
      (node (ref "U14") (pin "35") (pinfunction "RC4/SDI1/SDA1_35") (pintype "bidirectional"))
    )
    (net (code "70") (name "/RC_SERVO_8") (class "Default")
      (node (ref "J20") (pin "12") (pinfunction "12_12") (pintype "passive"))
      (node (ref "U14") (pin "36") (pinfunction "RC5/SDO1_36") (pintype "bidirectional"))
    )
    (net (code "71") (name "/RX0") (class "Default")
      (node (ref "J14") (pin "4") (pinfunction "4_4") (pintype "passive"))
      (node (ref "J3") (pin "4") (pinfunction "4_4") (pintype "passive"))
    )
    (net (code "72") (name "/RX1") (class "Default")
      (node (ref "J12") (pin "4") (pinfunction "4_4") (pintype "passive"))
      (node (ref "J3") (pin "6") (pinfunction "6_6") (pintype "passive"))
    )
    (net (code "73") (name "/SCL") (class "Default")
      (node (ref "J20") (pin "47") (pinfunction "47_47") (pintype "passive"))
      (node (ref "J20") (pin "50") (pinfunction "50_50") (pintype "passive"))
      (node (ref "J6") (pin "47") (pinfunction "47_47") (pintype "passive"))
      (node (ref "J6") (pin "50") (pinfunction "50_50") (pintype "passive"))
      (node (ref "U14") (pin "50") (pinfunction "RD6/PSP6/SCK2/SCL2_50") (pintype "bidirectional"))
    )
    (net (code "74") (name "/SCL_BFIN") (class "Default")
      (node (ref "J3") (pin "14") (pinfunction "14_14") (pintype "passive"))
      (node (ref "U9") (pin "3") (pinfunction "SCL1_3") (pintype "bidirectional"))
    )
    (net (code "75") (name "/SDA") (class "Default")
      (node (ref "J20") (pin "48") (pinfunction "48_48") (pintype "passive"))
      (node (ref "J20") (pin "51") (pinfunction "51_51") (pintype "passive"))
      (node (ref "J6") (pin "46") (pinfunction "46_46") (pintype "passive"))
      (node (ref "J6") (pin "49") (pinfunction "49_49") (pintype "passive"))
      (node (ref "U14") (pin "51") (pinfunction "RD5/PSP5/SDI2/SDA2_51") (pintype "bidirectional"))
    )
    (net (code "76") (name "/SDA_BFIN") (class "Default")
      (node (ref "J3") (pin "15") (pinfunction "15_15") (pintype "passive"))
      (node (ref "U9") (pin "4") (pinfunction "SDA1_4") (pintype "bidirectional"))
    )
    (net (code "77") (name "/SPI_SEL") (class "Default")
      (node (ref "J11") (pin "4") (pinfunction "4_4") (pintype "passive"))
      (node (ref "J16") (pin "4") (pinfunction "4_4") (pintype "passive"))
      (node (ref "J3") (pin "12") (pinfunction "12_12") (pintype "passive"))
    )
    (net (code "78") (name "/SPI_SEL2") (class "Default")
      (node (ref "J3") (pin "13") (pinfunction "13_13") (pintype "passive"))
    )
    (net (code "79") (name "/TMR2") (class "Default")
      (node (ref "J16") (pin "1") (pinfunction "1_1") (pintype "passive"))
      (node (ref "J3") (pin "7") (pinfunction "7_7") (pintype "passive"))
    )
    (net (code "80") (name "/TMR3") (class "Default")
      (node (ref "J16") (pin "2") (pinfunction "2_2") (pintype "passive"))
      (node (ref "J3") (pin "8") (pinfunction "8_8") (pintype "passive"))
    )
    (net (code "81") (name "/TX0") (class "Default")
      (node (ref "J14") (pin "3") (pinfunction "3_3") (pintype "passive"))
      (node (ref "J3") (pin "3") (pinfunction "3_3") (pintype "passive"))
    )
    (net (code "82") (name "/TX1") (class "Default")
      (node (ref "J12") (pin "3") (pinfunction "3_3") (pintype "passive"))
      (node (ref "J3") (pin "5") (pinfunction "5_5") (pintype "passive"))
    )
    (net (code "83") (name "/~{RST}") (class "Default")
      (node (ref "J7") (pin "1") (pinfunction "1_1") (pintype "passive"))
      (node (ref "R21") (pin "2") (pinfunction "2_2") (pintype "passive"))
      (node (ref "U13") (pin "1") (pinfunction "VO_1") (pintype "output"))
      (node (ref "U14") (pin "7") (pinfunction "~{MCLR/}RG5_7") (pintype "input"))
    )
    (net (code "84") (name "3.3V") (class "Default")
      (node (ref "C1") (pin "A") (pinfunction "+_A") (pintype "passive"))
      (node (ref "J15") (pin "1") (pinfunction "1_1") (pintype "passive"))
      (node (ref "J15") (pin "3") (pinfunction "3_3") (pintype "passive"))
      (node (ref "J3") (pin "1") (pinfunction "1_1") (pintype "passive"))
      (node (ref "LED1") (pin "A") (pinfunction "A_A") (pintype "passive"))
      (node (ref "U1") (pin "3") (pinfunction "OUT_3") (pintype "bidirectional"))
      (node (ref "U9") (pin "2") (pinfunction "VR1_2") (pintype "bidirectional"))
    )
    (net (code "85") (name "GND") (class "Default")
      (node (ref "C1") (pin "C") (pinfunction "-_C") (pintype "passive"))
      (node (ref "C10") (pin "1") (pinfunction "1_1") (pintype "passive"))
      (node (ref "C11") (pin "1") (pinfunction "1_1") (pintype "passive"))
      (node (ref "C12") (pin "2") (pinfunction "2_2") (pintype "passive"))
      (node (ref "C13") (pin "2") (pinfunction "2_2") (pintype "passive"))
      (node (ref "C14") (pin "2") (pinfunction "2_2") (pintype "passive"))
      (node (ref "C15") (pin "-") (pinfunction "-_-") (pintype "passive"))
      (node (ref "C16") (pin "2") (pinfunction "2_2") (pintype "passive"))
      (node (ref "C17") (pin "-") (pinfunction "-_-") (pintype "passive"))
      (node (ref "C2") (pin "2") (pinfunction "-_2") (pintype "passive"))
      (node (ref "C22") (pin "2") (pinfunction "2_2") (pintype "passive"))
      (node (ref "C23") (pin "2") (pinfunction "2_2") (pintype "passive"))
      (node (ref "C24") (pin "2") (pinfunction "-_2") (pintype "passive"))
      (node (ref "C25") (pin "2") (pinfunction "2_2") (pintype "passive"))
      (node (ref "C27") (pin "1") (pinfunction "1_1") (pintype "passive"))
      (node (ref "C3") (pin "1") (pinfunction "1_1") (pintype "passive"))
      (node (ref "C4") (pin "-") (pinfunction "-_-") (pintype "passive"))
      (node (ref "C5") (pin "-") (pinfunction "-_-") (pintype "passive"))
      (node (ref "C6") (pin "-") (pinfunction "-_-") (pintype "passive"))
      (node (ref "C7") (pin "2") (pinfunction "2_2") (pintype "passive"))
      (node (ref "C8") (pin "-") (pinfunction "-_-") (pintype "passive"))
      (node (ref "C9") (pin "2") (pinfunction "2_2") (pintype "passive"))
      (node (ref "D1") (pin "A") (pinfunction "A_A") (pintype "passive"))
      (node (ref "J11") (pin "5") (pinfunction "5_5") (pintype "passive"))
      (node (ref "J12") (pin "2") (pinfunction "2_2") (pintype "passive"))
      (node (ref "J13") (pin "3") (pinfunction "3_3") (pintype "passive"))
      (node (ref "J14") (pin "2") (pinfunction "2_2") (pintype "passive"))
      (node (ref "J15") (pin "2") (pinfunction "2_2") (pintype "passive"))
      (node (ref "J15") (pin "4") (pinfunction "4_4") (pintype "passive"))
      (node (ref "J16") (pin "3") (pinfunction "3_3") (pintype "passive"))
      (node (ref "J20") (pin "1") (pinfunction "1_1") (pintype "passive"))
      (node (ref "J20") (pin "10") (pinfunction "10_10") (pintype "passive"))
      (node (ref "J20") (pin "13") (pinfunction "13_13") (pintype "passive"))
      (node (ref "J20") (pin "16") (pinfunction "16_16") (pintype "passive"))
      (node (ref "J20") (pin "19") (pinfunction "19_19") (pintype "passive"))
      (node (ref "J20") (pin "22") (pinfunction "22_22") (pintype "passive"))
      (node (ref "J20") (pin "25") (pinfunction "25_25") (pintype "passive"))
      (node (ref "J20") (pin "28") (pinfunction "28_28") (pintype "passive"))
      (node (ref "J20") (pin "31") (pinfunction "31_31") (pintype "passive"))
      (node (ref "J20") (pin "34") (pinfunction "34_34") (pintype "passive"))
      (node (ref "J20") (pin "37") (pinfunction "37_37") (pintype "passive"))
      (node (ref "J20") (pin "4") (pinfunction "4_4") (pintype "passive"))
      (node (ref "J20") (pin "40") (pinfunction "40_40") (pintype "passive"))
      (node (ref "J20") (pin "43") (pinfunction "43_43") (pintype "passive"))
      (node (ref "J20") (pin "46") (pinfunction "46_46") (pintype "passive"))
      (node (ref "J20") (pin "49") (pinfunction "49_49") (pintype "passive"))
      (node (ref "J20") (pin "7") (pinfunction "7_7") (pintype "passive"))
      (node (ref "J3") (pin "16") (pinfunction "16_16") (pintype "passive"))
      (node (ref "J3") (pin "2") (pinfunction "2_2") (pintype "passive"))
      (node (ref "J4") (pin "5") (pinfunction "5_5") (pintype "passive"))
      (node (ref "J5") (pin "2") (pinfunction "2_2") (pintype "passive"))
      (node (ref "J6") (pin "12") (pinfunction "12_12") (pintype "passive"))
      (node (ref "J6") (pin "15") (pinfunction "15_15") (pintype "passive"))
      (node (ref "J6") (pin "18") (pinfunction "18_18") (pintype "passive"))
      (node (ref "J6") (pin "21") (pinfunction "21_21") (pintype "passive"))
      (node (ref "J6") (pin "24") (pinfunction "24_24") (pintype "passive"))
      (node (ref "J6") (pin "27") (pinfunction "27_27") (pintype "passive"))
      (node (ref "J6") (pin "3") (pinfunction "3_3") (pintype "passive"))
      (node (ref "J6") (pin "30") (pinfunction "30_30") (pintype "passive"))
      (node (ref "J6") (pin "33") (pinfunction "33_33") (pintype "passive"))
      (node (ref "J6") (pin "36") (pinfunction "36_36") (pintype "passive"))
      (node (ref "J6") (pin "39") (pinfunction "39_39") (pintype "passive"))
      (node (ref "J6") (pin "42") (pinfunction "42_42") (pintype "passive"))
      (node (ref "J6") (pin "45") (pinfunction "45_45") (pintype "passive"))
      (node (ref "J6") (pin "48") (pinfunction "48_48") (pintype "passive"))
      (node (ref "J6") (pin "51") (pinfunction "51_51") (pintype "passive"))
      (node (ref "J6") (pin "6") (pinfunction "6_6") (pintype "passive"))
      (node (ref "J6") (pin "9") (pinfunction "9_9") (pintype "passive"))
      (node (ref "J7") (pin "3") (pinfunction "3_3") (pintype "passive"))
      (node (ref "J8") (pin "5") (pinfunction "5_5") (pintype "passive"))
      (node (ref "R23") (pin "1") (pinfunction "1_1") (pintype "passive"))
      (node (ref "U1") (pin "2") (pinfunction "GND_2") (pintype "bidirectional"))
      (node (ref "U11") (pin "1") (pinfunction "GND_1") (pintype "bidirectional"))
      (node (ref "U13") (pin "3") (pinfunction "GND_3") (pintype "passive"))
      (node (ref "U14") (pin "20") (pinfunction "AVSS_20") (pintype "power_in"))
      (node (ref "U14") (pin "25") (pinfunction "VSS_25") (pintype "power_in"))
      (node (ref "U14") (pin "41") (pinfunction "VSS_41") (pintype "power_in"))
      (node (ref "U14") (pin "56") (pinfunction "VSS_56") (pintype "power_in"))
      (node (ref "U14") (pin "9") (pinfunction "VSS_9") (pintype "power_in"))
      (node (ref "U15") (pin "10") (pinfunction "GND_10") (pintype "power_in"))
      (node (ref "U15") (pin "2") (pinfunction "RTRY_2") (pintype "input"))
      (node (ref "U15") (pin "8") (pinfunction "LSS_8") (pintype "output"))
      (node (ref "U15") (pin "PAD") (pinfunction "PAD_PAD") (pintype "output"))
      (node (ref "U2") (pin "3") (pinfunction "GND_3") (pintype "bidirectional"))
      (node (ref "U2") (pin "5") (pinfunction "SD_5") (pintype "bidirectional"))
      (node (ref "U2") (pin "6") (pinfunction "GND_6") (pintype "bidirectional"))
      (node (ref "U3") (pin "10") (pinfunction "GND_10") (pintype "power_in"))
      (node (ref "U3") (pin "2") (pinfunction "RTRY_2") (pintype "input"))
      (node (ref "U3") (pin "8") (pinfunction "LSS_8") (pintype "output"))
      (node (ref "U3") (pin "PAD") (pinfunction "PAD_PAD") (pintype "output"))
      (node (ref "U4") (pin "10") (pinfunction "GND_10") (pintype "power_in"))
      (node (ref "U4") (pin "2") (pinfunction "RTRY_2") (pintype "input"))
      (node (ref "U4") (pin "8") (pinfunction "LSS_8") (pintype "output"))
      (node (ref "U4") (pin "PAD") (pinfunction "PAD_PAD") (pintype "output"))
      (node (ref "U5") (pin "10") (pinfunction "GND_10") (pintype "power_in"))
      (node (ref "U5") (pin "2") (pinfunction "RTRY_2") (pintype "input"))
      (node (ref "U5") (pin "8") (pinfunction "LSS_8") (pintype "output"))
      (node (ref "U5") (pin "PAD") (pinfunction "PAD_PAD") (pintype "output"))
      (node (ref "U9") (pin "1") (pinfunction "GND_1") (pintype "bidirectional"))
    )
    (net (code "86") (name "Net-(D2-A)") (class "Default")
      (node (ref "D2") (pin "2") (pinfunction "A_2") (pintype "passive"))
      (node (ref "J5") (pin "1") (pinfunction "1_1") (pintype "passive"))
    )
    (net (code "87") (name "Net-(D4-A)") (class "Default")
      (node (ref "D4") (pin "2") (pinfunction "A_2") (pintype "passive"))
      (node (ref "J20") (pin "14") (pinfunction "14_14") (pintype "passive"))
    )
    (net (code "88") (name "Net-(D4-C)") (class "Default")
      (node (ref "D4") (pin "1") (pinfunction "C_1") (pintype "passive"))
      (node (ref "J20") (pin "11") (pinfunction "11_11") (pintype "passive"))
      (node (ref "J20") (pin "2") (pinfunction "2_2") (pintype "passive"))
      (node (ref "J20") (pin "5") (pinfunction "5_5") (pintype "passive"))
      (node (ref "J20") (pin "8") (pinfunction "8_8") (pintype "passive"))
    )
    (net (code "89") (name "Net-(D6-A)") (class "Default")
      (node (ref "D6") (pin "2") (pinfunction "A_2") (pintype "passive"))
      (node (ref "J6") (pin "14") (pinfunction "14_14") (pintype "passive"))
    )
    (net (code "90") (name "Net-(D6-C)") (class "Default")
      (node (ref "D6") (pin "1") (pinfunction "C_1") (pintype "passive"))
      (node (ref "J6") (pin "11") (pinfunction "11_11") (pintype "passive"))
      (node (ref "J6") (pin "2") (pinfunction "2_2") (pintype "passive"))
      (node (ref "J6") (pin "5") (pinfunction "5_5") (pintype "passive"))
      (node (ref "J6") (pin "8") (pinfunction "8_8") (pintype "passive"))
    )
    (net (code "91") (name "Net-(LED1-PadC)") (class "Default")
      (node (ref "LED1") (pin "C") (pinfunction "C_C") (pintype "passive"))
      (node (ref "R19") (pin "1") (pinfunction "1_1") (pintype "passive"))
    )
    (net (code "92") (name "Net-(U2-FB)") (class "Default")
      (node (ref "R22") (pin "1") (pinfunction "1_1") (pintype "passive"))
      (node (ref "R23") (pin "2") (pinfunction "2_2") (pintype "passive"))
      (node (ref "U2") (pin "4") (pinfunction "FB_4") (pintype "bidirectional"))
    )
    (net (code "93") (name "Net-(U2-OUT)") (class "Default")
      (node (ref "D1") (pin "C") (pinfunction "C_C") (pintype "passive"))
      (node (ref "L1") (pin "1") (pinfunction "1_1") (pintype "passive"))
      (node (ref "U2") (pin "2") (pinfunction "OUT_2") (pintype "bidirectional"))
    )
    (net (code "94") (name "Net-(U3-OUT1)") (class "Default")
      (node (ref "J2") (pin "3") (pinfunction "3_3") (pintype "passive"))
      (node (ref "U3") (pin "7") (pinfunction "OUT1_7") (pintype "output"))
    )
    (net (code "95") (name "Net-(U3-OUT2)") (class "Default")
      (node (ref "J2") (pin "4") (pinfunction "4_4") (pintype "passive"))
      (node (ref "U3") (pin "9") (pinfunction "OUT2_9") (pintype "input"))
    )
    (net (code "96") (name "Net-(U4-OUT1)") (class "Default")
      (node (ref "J1") (pin "2") (pinfunction "2_2") (pintype "passive"))
      (node (ref "U4") (pin "7") (pinfunction "OUT1_7") (pintype "output"))
    )
    (net (code "97") (name "Net-(U4-OUT2)") (class "Default")
      (node (ref "J1") (pin "1") (pinfunction "1_1") (pintype "passive"))
      (node (ref "U4") (pin "9") (pinfunction "OUT2_9") (pintype "input"))
    )
    (net (code "98") (name "Net-(U5-OUT1)") (class "Default")
      (node (ref "J1") (pin "4") (pinfunction "4_4") (pintype "passive"))
      (node (ref "U5") (pin "7") (pinfunction "OUT1_7") (pintype "output"))
    )
    (net (code "99") (name "Net-(U5-OUT2)") (class "Default")
      (node (ref "J1") (pin "3") (pinfunction "3_3") (pintype "passive"))
      (node (ref "U5") (pin "9") (pinfunction "OUT2_9") (pintype "input"))
    )
    (net (code "100") (name "Net-(U9-EN)") (class "Default")
      (node (ref "C27") (pin "2") (pinfunction "2_2") (pintype "passive"))
      (node (ref "R32") (pin "1") (pinfunction "1_1") (pintype "passive"))
      (node (ref "U9") (pin "7") (pinfunction "VR2_7") (pintype "bidirectional"))
      (node (ref "U9") (pin "8") (pinfunction "EN_8") (pintype "input"))
    )
    (net (code "101") (name "Net-(U9-SCL2)") (class "Default")
      (node (ref "R33") (pin "1") (pinfunction "1_1") (pintype "passive"))
      (node (ref "U9") (pin "6") (pinfunction "SCL2_6") (pintype "bidirectional"))
    )
    (net (code "102") (name "Net-(U9-SDA2)") (class "Default")
      (node (ref "R34") (pin "1") (pinfunction "1_1") (pintype "passive"))
      (node (ref "U9") (pin "5") (pinfunction "SDA2_5") (pintype "bidirectional"))
    )
    (net (code "103") (name "Net-(U14-AVDD)") (class "Default")
      (node (ref "C9") (pin "1") (pinfunction "1_1") (pintype "passive"))
      (node (ref "U14") (pin "19") (pinfunction "AVDD_19") (pintype "power_in"))
    )
    (net (code "104") (name "Net-(U14-VDDCORE{slash}VCAP)") (class "Default")
      (node (ref "C3") (pin "2") (pinfunction "2_2") (pintype "passive"))
      (node (ref "U14") (pin "10") (pinfunction "VDDCORE/VCAP_10") (pintype "power_in"))
    )
    (net (code "105") (name "Net-(U15-OUT1)") (class "Default")
      (node (ref "J2") (pin "1") (pinfunction "1_1") (pintype "passive"))
      (node (ref "U15") (pin "7") (pinfunction "OUT1_7") (pintype "output"))
    )
    (net (code "106") (name "Net-(U15-OUT2)") (class "Default")
      (node (ref "J2") (pin "2") (pinfunction "2_2") (pintype "passive"))
      (node (ref "U15") (pin "9") (pinfunction "OUT2_9") (pintype "input"))
    )
    (net (code "107") (name "unconnected-(J4-Pad4)") (class "Default")
      (node (ref "J4") (pin "4") (pinfunction "4_4") (pintype "passive"))
    )
    (net (code "108") (name "unconnected-(J12-Pad1)") (class "Default")
      (node (ref "J12") (pin "1") (pinfunction "1_1") (pintype "passive"))
    )
    (net (code "109") (name "unconnected-(J14-Pad1)") (class "Default")
      (node (ref "J14") (pin "1") (pinfunction "1_1") (pintype "passive"))
    )
    (net (code "110") (name "unconnected-(R19-Pad2)") (class "Default")
      (node (ref "R19") (pin "2") (pinfunction "2_2") (pintype "passive"))
    )
    (net (code "111") (name "unconnected-(U$1-1-PadP$2)") (class "Default")
      (node (ref "U$1") (pin "P$2") (pinfunction "1_P$2") (pintype "bidirectional"))
    )
    (net (code "112") (name "unconnected-(U$2-1-PadP$2)") (class "Default")
      (node (ref "U$2") (pin "P$2") (pinfunction "1_P$2") (pintype "bidirectional"))
    )
    (net (code "113") (name "unconnected-(U$7-1-PadP$2)") (class "Default")
      (node (ref "U$7") (pin "P$2") (pinfunction "1_P$2") (pintype "bidirectional"))
    )
    (net (code "114") (name "unconnected-(U$8-1-PadP$2)") (class "Default")
      (node (ref "U$8") (pin "P$2") (pinfunction "1_P$2") (pintype "bidirectional"))
    )
    (net (code "115") (name "unconnected-(U3-FAULT-Pad1)") (class "Default")
      (node (ref "U3") (pin "1") (pinfunction "FAULT_1") (pintype "output"))
    )
    (net (code "116") (name "unconnected-(U4-FAULT-Pad1)") (class "Default")
      (node (ref "U4") (pin "1") (pinfunction "FAULT_1") (pintype "output"))
    )
    (net (code "117") (name "unconnected-(U5-FAULT-Pad1)") (class "Default")
      (node (ref "U5") (pin "1") (pinfunction "FAULT_1") (pintype "output"))
    )
    (net (code "118") (name "unconnected-(U14-RE0{slash}~{RD{slash}}P2D-Pad2)") (class "Default")
      (node (ref "U14") (pin "2") (pinfunction "RE0/~{RD/}P2D_2") (pintype "bidirectional"))
    )
    (net (code "119") (name "unconnected-(U14-RE1{slash}~{WR{slash}}P2C-Pad1)") (class "Default")
      (node (ref "U14") (pin "1") (pinfunction "RE1/~{WR/}P2C_1") (pintype "bidirectional"))
    )
    (net (code "120") (name "unconnected-(U14-RG0{slash}ECCP3{slash}P3A-Pad3)") (class "Default")
      (node (ref "U14") (pin "3") (pinfunction "RG0/ECCP3/P3A_3") (pintype "bidirectional"))
    )
    (net (code "121") (name "unconnected-(U15-FAULT-Pad1)") (class "Default")
      (node (ref "U15") (pin "1") (pinfunction "FAULT_1") (pintype "output"))
    )
  )
)
